# Demux.net
KiCad netlist of a schematic drawn in Altium Designer
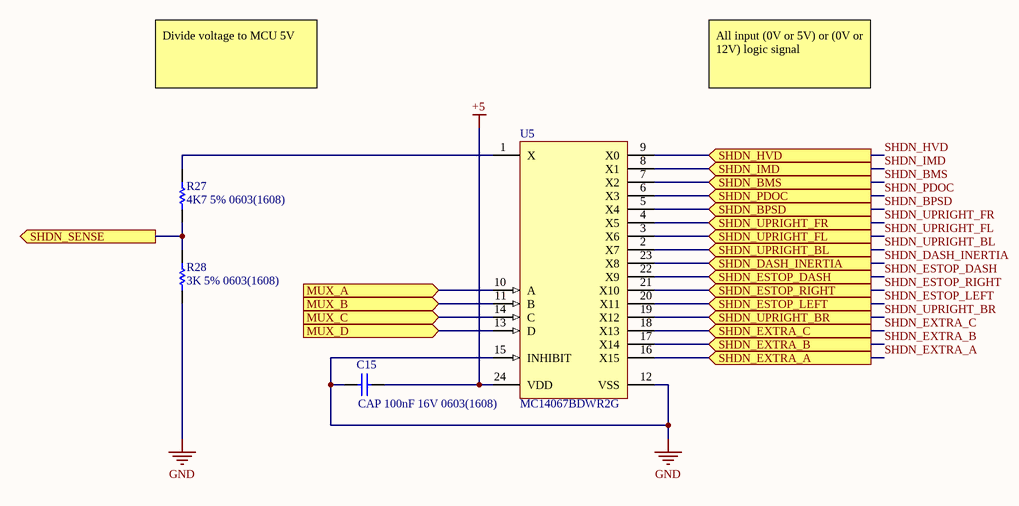
[diagram p0: Demux.SchDoc]

(export (version "E")
  (design (tool "Eeschema 10.0.6"))
  (components
    (comp (ref "C15")
      (value "CAP 100nF 16V 0603(1608)")
      (footprint "CAPC0603(1608)100_M")
      (description "CAP 100nF 16V ±5% 0603 (1608 Metric) Thickness 1mm SMD")
      (fields (field (name "TOLERANCE") "Â±5%"))
      (libsource (lib "Altium Content Vault") (part "CAP"))
    )
    (comp (ref "R27")
      (value "4K7 5% 0603(1608)")
      (footprint "RESC0603(1608)_N")
      (description "4K7 0.1W 5% 0603 (1608 Metric)  SMD")
      (fields (field (name "TOLERANCE") "5 %") (field (name "POWER") "0.1 W"))
      (libsource (lib "Altium Content Vault") (part "RES"))
    )
    (comp (ref "R28")
      (value "3K 5% 0603(1608)")
      (footprint "RESC0603(1608)_M")
      (description "3K 0.1W 5% 0603 (1608 Metric)  SMD")
      (fields (field (name "POWER") "0.1 W") (field (name "TOLERANCE") "5 %"))
      (libsource (lib "Altium Content Vault") (part "RES"))
    )
    (comp (ref "U5")
      (value "MC14067BDWR2G")
      (footprint "ONSC-SOIC-24-751E-04_V")
      (fields (field (name "MANUFACTURER") "On Semiconductor"))
      (libsource (lib "Altium Content Vault") (part "ONSC-MC14067B-SOIC-24-751E-04"))
    )
  )
  (nets
    (net (code "1") (name "+5") (class "Default")
      (node (ref "C15") (pin "2") (pinfunction "2_2") (pintype "passive"))
      (node (ref "U5") (pin "24") (pinfunction "VDD_24") (pintype "power_in"))
    )
    (net (code "2") (name "/MUX_A") (class "Default")
      (node (ref "U5") (pin "10") (pinfunction "A_10") (pintype "input"))
    )
    (net (code "3") (name "/MUX_B") (class "Default")
      (node (ref "U5") (pin "11") (pinfunction "B_11") (pintype "input"))
    )
    (net (code "4") (name "/MUX_C") (class "Default")
      (node (ref "U5") (pin "14") (pinfunction "C_14") (pintype "input"))
    )
    (net (code "5") (name "/MUX_D") (class "Default")
      (node (ref "U5") (pin "13") (pinfunction "D_13") (pintype "input"))
    )
    (net (code "6") (name "/SHDN_BMS") (class "Default")
      (node (ref "U5") (pin "7") (pinfunction "X2_7") (pintype "passive"))
    )
    (net (code "7") (name "/SHDN_BPSD") (class "Default")
      (node (ref "U5") (pin "5") (pinfunction "X4_5") (pintype "passive"))
    )
    (net (code "8") (name "/SHDN_DASH_INERTIA") (class "Default")
      (node (ref "U5") (pin "23") (pinfunction "X8_23") (pintype "passive"))
    )
    (net (code "9") (name "/SHDN_ESTOP_DASH") (class "Default")
      (node (ref "U5") (pin "22") (pinfunction "X9_22") (pintype "passive"))
    )
    (net (code "10") (name "/SHDN_ESTOP_LEFT") (class "Default")
      (node (ref "U5") (pin "20") (pinfunction "X11_20") (pintype "passive"))
    )
    (net (code "11") (name "/SHDN_ESTOP_RIGHT") (class "Default")
      (node (ref "U5") (pin "21") (pinfunction "X10_21") (pintype "passive"))
    )
    (net (code "12") (name "/SHDN_EXTRA_A") (class "Default")
      (node (ref "U5") (pin "16") (pinfunction "X15_16") (pintype "passive"))
    )
    (net (code "13") (name "/SHDN_EXTRA_B") (class "Default")
      (node (ref "U5") (pin "17") (pinfunction "X14_17") (pintype "passive"))
    )
    (net (code "14") (name "/SHDN_EXTRA_C") (class "Default")
      (node (ref "U5") (pin "18") (pinfunction "X13_18") (pintype "passive"))
    )
    (net (code "15") (name "/SHDN_HVD") (class "Default")
      (node (ref "U5") (pin "9") (pinfunction "X0_9") (pintype "passive"))
    )
    (net (code "16") (name "/SHDN_IMD") (class "Default")
      (node (ref "U5") (pin "8") (pinfunction "X1_8") (pintype "passive"))
    )
    (net (code "17") (name "/SHDN_PDOC") (class "Default")
      (node (ref "U5") (pin "6") (pinfunction "X3_6") (pintype "passive"))
    )
    (net (code "18") (name "/SHDN_SENSE") (class "Default")
      (node (ref "R27") (pin "1") (pinfunction "1_1") (pintype "passive"))
      (node (ref "R28") (pin "2") (pinfunction "2_2") (pintype "passive"))
    )
    (net (code "19") (name "/SHDN_UPRIGHT_BL") (class "Default")
      (node (ref "U5") (pin "2") (pinfunction "X7_2") (pintype "passive"))
    )
    (net (code "20") (name "/SHDN_UPRIGHT_BR") (class "Default")
      (node (ref "U5") (pin "19") (pinfunction "X12_19") (pintype "passive"))
    )
    (net (code "21") (name "/SHDN_UPRIGHT_FL") (class "Default")
      (node (ref "U5") (pin "3") (pinfunction "X6_3") (pintype "passive"))
    )
    (net (code "22") (name "/SHDN_UPRIGHT_FR") (class "Default")
      (node (ref "U5") (pin "4") (pinfunction "X5_4") (pintype "passive"))
    )
    (net (code "23") (name "GND") (class "Default")
      (node (ref "C15") (pin "1") (pinfunction "1_1") (pintype "passive"))
      (node (ref "R28") (pin "1") (pinfunction "1_1") (pintype "passive"))
      (node (ref "U5") (pin "12") (pinfunction "VSS_12") (pintype "power_in"))
      (node (ref "U5") (pin "15") (pinfunction "INHIBIT_15") (pintype "input"))
    )
    (net (code "24") (name "Net-(U5-X)") (class "Default")
      (node (ref "R27") (pin "2") (pinfunction "2_2") (pintype "passive"))
      (node (ref "U5") (pin "1") (pinfunction "X_1") (pintype "passive"))
    )
  )
)
